# blinkm_mk2b.net
KiCad netlist of a schematic drawn in EAGLE
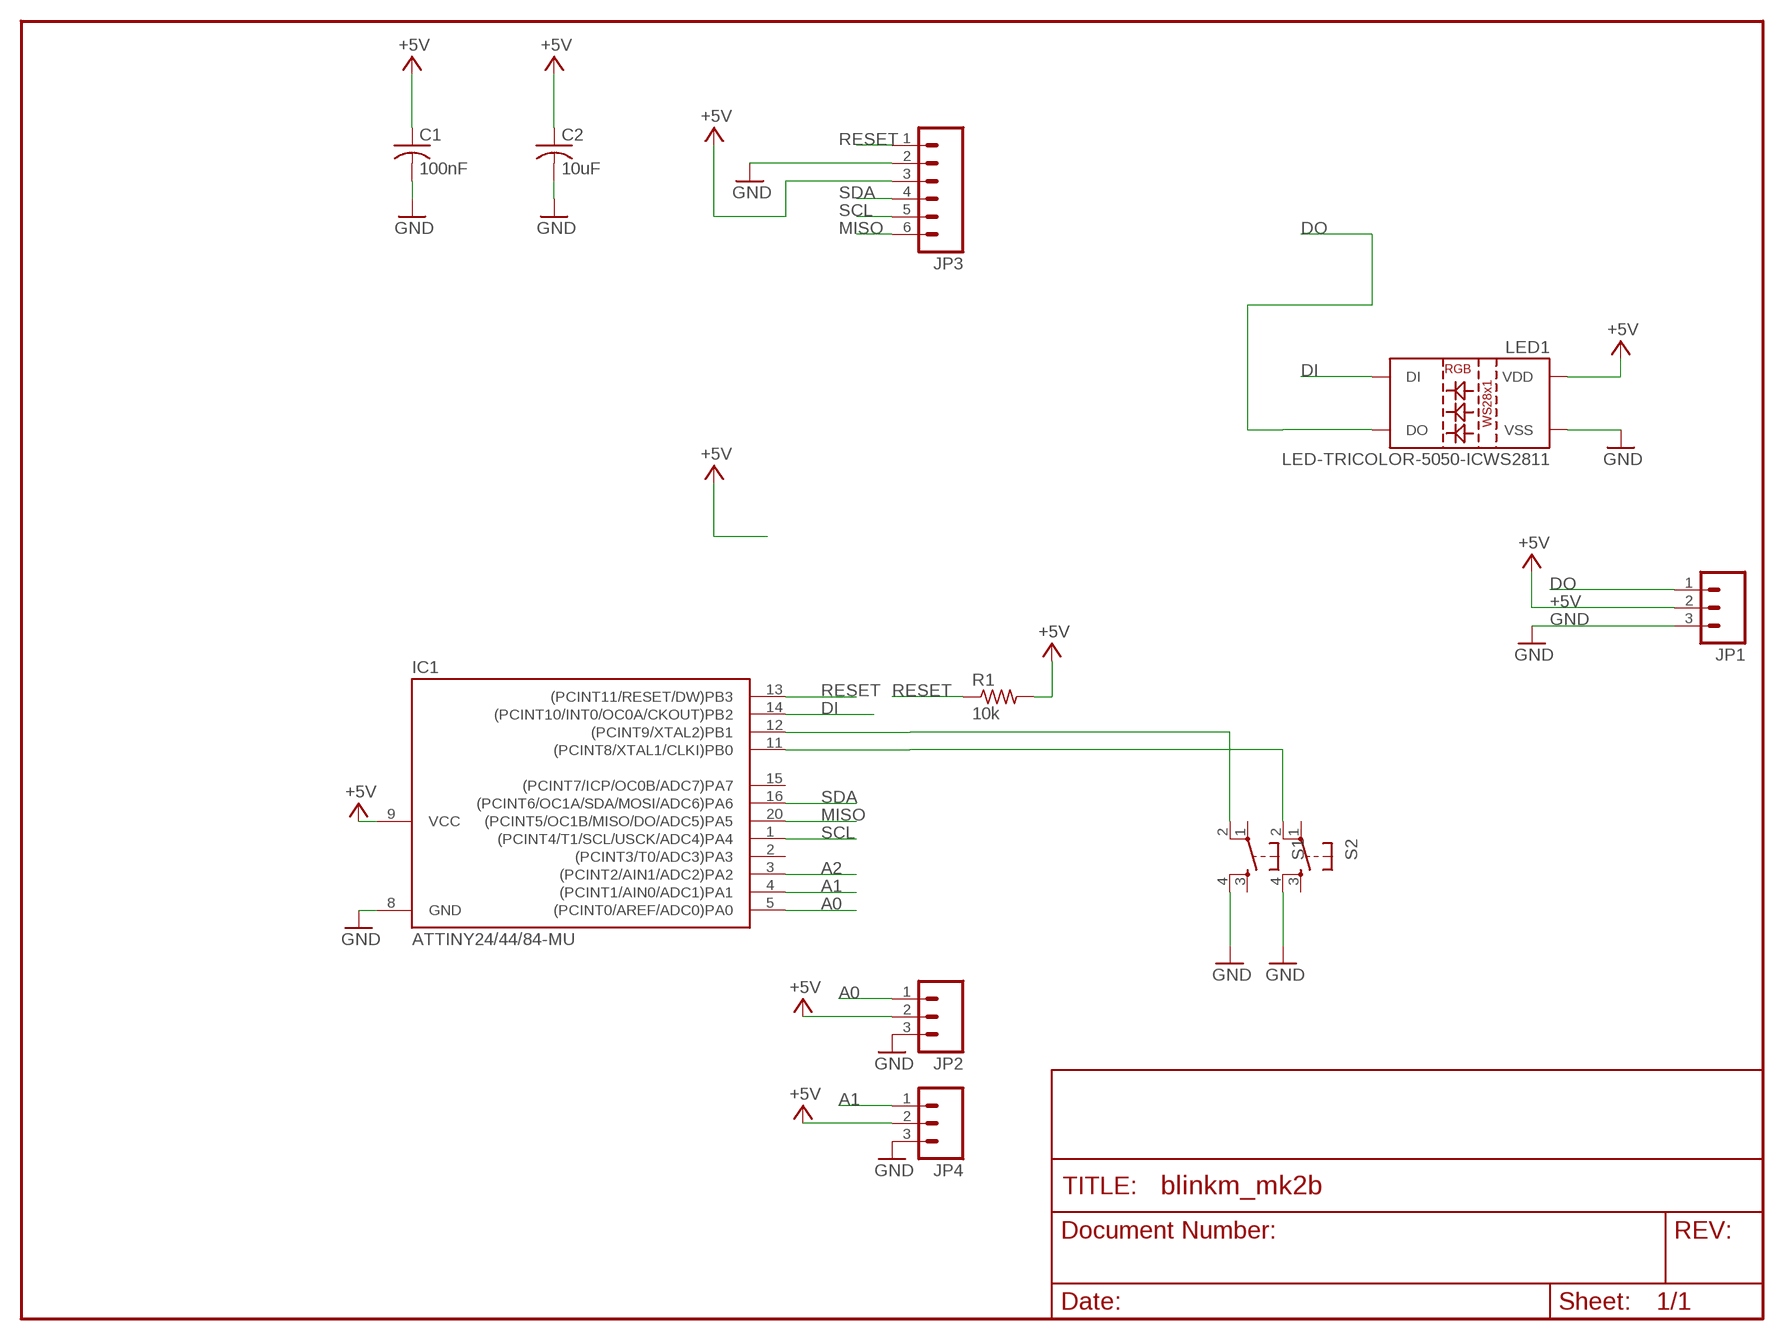
[diagram p0: schematic, sheet 1]

(export (version "E")
  (design (tool "Eeschema 10.0.6"))
  (components
    (comp (ref "C1")
      (value "100nF")
      (footprint "eagle-import:C0603")
      (libsource (lib "eagle-import") (part "C-USC0603"))
    )
    (comp (ref "C2")
      (value "10uF")
      (footprint "eagle-import:C0603")
      (libsource (lib "eagle-import") (part "C-USC0603"))
    )
    (comp (ref "IC1")
      (value "ATTINY24/44/84-MU")
      (footprint "eagle-import:QFN_MLF20")
      (libsource (lib "eagle-import") (part "ATTINY24/44/84-MU"))
    )
    (comp (ref "JP1")
      (value "M03PTH")
      (footprint "eagle-import:1X03")
      (libsource (lib "eagle-import") (part "M03PTH"))
    )
    (comp (ref "JP2")
      (value "M03PTH")
      (footprint "eagle-import:1X03")
      (libsource (lib "eagle-import") (part "M03PTH"))
    )
    (comp (ref "JP3")
      (value "M06SIP")
      (footprint "eagle-import:1X06")
      (libsource (lib "eagle-import") (part "M06SIP"))
    )
    (comp (ref "JP4")
      (value "M03PTH")
      (footprint "eagle-import:1X03")
      (libsource (lib "eagle-import") (part "M03PTH"))
    )
    (comp (ref "LED1")
      (value "LED-TRICOLOR-5050-ICWS2811")
      (footprint "eagle-import:LED-TRICOLOR-5050-IC")
      (libsource (lib "eagle-import") (part "LED-TRICOLOR-5050-ICWS2811"))
    )
    (comp (ref "R1")
      (value "10k")
      (footprint "eagle-import:R0603")
      (libsource (lib "eagle-import") (part "R-US_R0603"))
    )
    (comp (ref "S1")
      (value "TAC_SWITCHSMD")
      (footprint "eagle-import:TACTILE_SWITCH_SMD")
      (libsource (lib "eagle-import") (part "TAC_SWITCHSMD"))
    )
    (comp (ref "S2")
      (value "TAC_SWITCHSMD")
      (footprint "eagle-import:TACTILE_SWITCH_SMD")
      (libsource (lib "eagle-import") (part "TAC_SWITCHSMD"))
    )
  )
  (nets
    (net (code "1") (name "+5V") (class "Default")
      (node (ref "C1") (pin "1") (pinfunction "1_1") (pintype "passive"))
      (node (ref "C2") (pin "1") (pinfunction "1_1") (pintype "passive"))
      (node (ref "IC1") (pin "9") (pinfunction "VCC_9") (pintype "power_in"))
      (node (ref "JP1") (pin "2") (pinfunction "2_2") (pintype "passive"))
      (node (ref "JP2") (pin "2") (pinfunction "2_2") (pintype "passive"))
      (node (ref "JP3") (pin "3") (pinfunction "3_3") (pintype "passive"))
      (node (ref "JP4") (pin "2") (pinfunction "2_2") (pintype "passive"))
      (node (ref "LED1") (pin "3") (pinfunction "VDD_3") (pintype "bidirectional"))
      (node (ref "LED1") (pin "5") (pinfunction "VDD_5") (pintype "bidirectional"))
      (node (ref "R1") (pin "2") (pinfunction "2_2") (pintype "passive"))
    )
    (net (code "2") (name "/A0") (class "Default")
      (node (ref "IC1") (pin "5") (pinfunction "(PCINT0/AREF/ADC0)PA0_5") (pintype "bidirectional"))
      (node (ref "JP2") (pin "1") (pinfunction "1_1") (pintype "passive"))
    )
    (net (code "3") (name "/A1") (class "Default")
      (node (ref "IC1") (pin "4") (pinfunction "(PCINT1/AIN0/ADC1)PA1_4") (pintype "bidirectional"))
      (node (ref "JP4") (pin "1") (pinfunction "1_1") (pintype "passive"))
    )
    (net (code "4") (name "/A2") (class "Default")
      (node (ref "IC1") (pin "3") (pinfunction "(PCINT2/AIN1/ADC2)PA2_3") (pintype "bidirectional"))
    )
    (net (code "5") (name "/DI") (class "Default")
      (node (ref "IC1") (pin "14") (pinfunction "(PCINT10/INT0/OC0A/CKOUT)PB2_14") (pintype "bidirectional"))
      (node (ref "LED1") (pin "2") (pinfunction "DI_2") (pintype "bidirectional"))
    )
    (net (code "6") (name "/DO") (class "Default")
      (node (ref "JP1") (pin "1") (pinfunction "1_1") (pintype "passive"))
      (node (ref "LED1") (pin "1") (pinfunction "DO_1") (pintype "bidirectional"))
    )
    (net (code "7") (name "/MISO") (class "Default")
      (node (ref "IC1") (pin "20") (pinfunction "(PCINT5/OC1B/MISO/DO/ADC5)PA5_20") (pintype "bidirectional"))
      (node (ref "JP3") (pin "6") (pinfunction "6_6") (pintype "passive"))
    )
    (net (code "8") (name "/RESET") (class "Default")
      (node (ref "IC1") (pin "13") (pinfunction "(PCINT11/RESET/DW)PB3_13") (pintype "bidirectional"))
      (node (ref "JP3") (pin "1") (pinfunction "1_1") (pintype "passive"))
      (node (ref "R1") (pin "1") (pinfunction "1_1") (pintype "passive"))
    )
    (net (code "9") (name "/SCL") (class "Default")
      (node (ref "IC1") (pin "1") (pinfunction "(PCINT4/T1/SCL/USCK/ADC4)PA4_1") (pintype "bidirectional"))
      (node (ref "JP3") (pin "5") (pinfunction "5_5") (pintype "passive"))
    )
    (net (code "10") (name "/SDA") (class "Default")
      (node (ref "IC1") (pin "16") (pinfunction "(PCINT6/OC1A/SDA/MOSI/ADC6)PA6_16") (pintype "bidirectional"))
      (node (ref "JP3") (pin "4") (pinfunction "4_4") (pintype "passive"))
    )
    (net (code "11") (name "GND") (class "Default")
      (node (ref "C1") (pin "2") (pinfunction "2_2") (pintype "passive"))
      (node (ref "C2") (pin "2") (pinfunction "2_2") (pintype "passive"))
      (node (ref "IC1") (pin "8") (pinfunction "GND_8") (pintype "power_in"))
      (node (ref "JP1") (pin "3") (pinfunction "3_3") (pintype "passive"))
      (node (ref "JP2") (pin "3") (pinfunction "3_3") (pintype "passive"))
      (node (ref "JP3") (pin "2") (pinfunction "2_2") (pintype "passive"))
      (node (ref "JP4") (pin "3") (pinfunction "3_3") (pintype "passive"))
      (node (ref "LED1") (pin "6") (pinfunction "VSS_6") (pintype "bidirectional"))
      (node (ref "S1") (pin "4") (pinfunction "4_4") (pintype "passive"))
      (node (ref "S2") (pin "4") (pinfunction "4_4") (pintype "passive"))
    )
    (net (code "12") (name "Net-(IC1-(PCINT8{slash}XTAL1{slash}CLKI)PB0)") (class "Default")
      (node (ref "IC1") (pin "11") (pinfunction "(PCINT8/XTAL1/CLKI)PB0_11") (pintype "bidirectional"))
      (node (ref "S2") (pin "2") (pinfunction "2_2") (pintype "passive"))
    )
    (net (code "13") (name "Net-(IC1-(PCINT9{slash}XTAL2)PB1)") (class "Default")
      (node (ref "IC1") (pin "12") (pinfunction "(PCINT9/XTAL2)PB1_12") (pintype "bidirectional"))
      (node (ref "S1") (pin "2") (pinfunction "2_2") (pintype "passive"))
    )
    (net (code "14") (name "unconnected-(IC1-(PCINT3{slash}T0{slash}ADC3)PA3-Pad2)") (class "Default")
      (node (ref "IC1") (pin "2") (pinfunction "(PCINT3/T0/ADC3)PA3_2") (pintype "bidirectional"))
    )
    (net (code "15") (name "unconnected-(IC1-(PCINT7{slash}ICP{slash}OC0B{slash}ADC7)PA7-Pad15)") (class "Default")
      (node (ref "IC1") (pin "15") (pinfunction "(PCINT7/ICP/OC0B/ADC7)PA7_15") (pintype "bidirectional"))
    )
    (net (code "16") (name "unconnected-(S1-Pad1)") (class "Default")
      (node (ref "S1") (pin "1") (pinfunction "1_1") (pintype "passive"))
    )
    (net (code "17") (name "unconnected-(S1-Pad3)") (class "Default")
      (node (ref "S1") (pin "3") (pinfunction "3_3") (pintype "passive"))
    )
    (net (code "18") (name "unconnected-(S2-Pad1)") (class "Default")
      (node (ref "S2") (pin "1") (pinfunction "1_1") (pintype "passive"))
    )
    (net (code "19") (name "unconnected-(S2-Pad3)") (class "Default")
      (node (ref "S2") (pin "3") (pinfunction "3_3") (pintype "passive"))
    )
  )
)
